# radio-v3_2.net
KiCad netlist of a schematic drawn in EAGLE
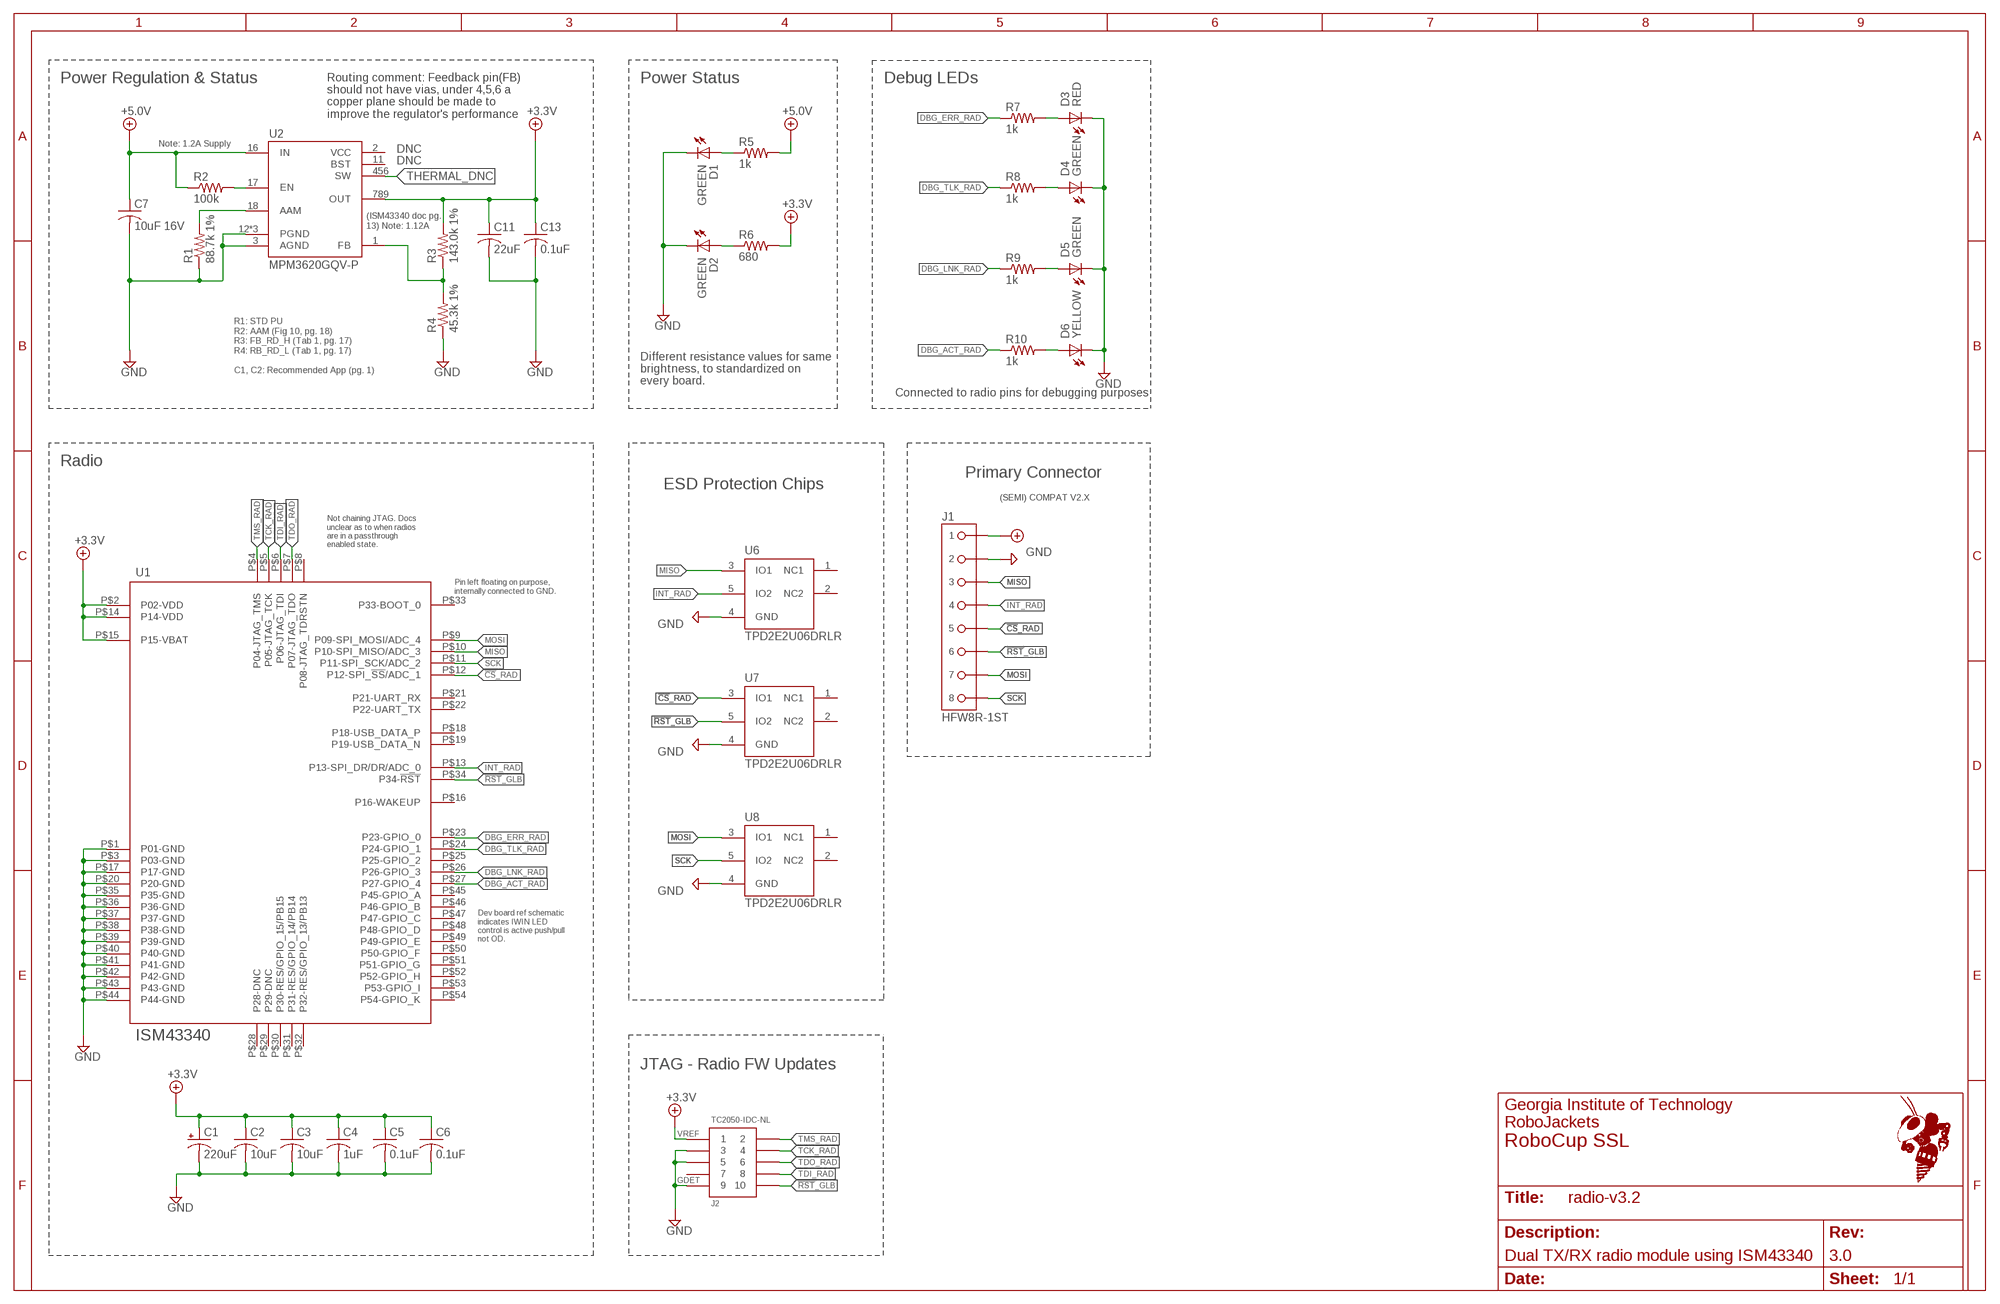
[diagram p0: schematic, sheet 1]

(export (version "E")
  (design (tool "Eeschema 10.0.6"))
  (components
    (comp (ref "C1")
      (value "220uF")
      (footprint "eagle-import:ECA-0JM221-HGT_HORIZ")
      (fields (field (name "MANUFACTURER_PART_NUMBER") "ECA-1HHG221"))
      (libsource (lib "eagle-import") (part "ECA-0JM221"))
    )
    (comp (ref "C2")
      (value "10uF")
      (footprint "eagle-import:C0805")
      (libsource (lib "eagle-import") (part "C-USC0805"))
    )
    (comp (ref "C3")
      (value "10uF")
      (footprint "eagle-import:C0805")
      (libsource (lib "eagle-import") (part "C-USC0805"))
    )
    (comp (ref "C4")
      (value "1uF")
      (footprint "eagle-import:C0603")
      (libsource (lib "eagle-import") (part "C-USC0603"))
    )
    (comp (ref "C5")
      (value "0.1uF")
      (footprint "eagle-import:C0603")
      (libsource (lib "eagle-import") (part "C-USC0603"))
    )
    (comp (ref "C6")
      (value "0.1uF")
      (footprint "eagle-import:C0603")
      (libsource (lib "eagle-import") (part "C-USC0603"))
    )
    (comp (ref "C7")
      (value "10uF 16V")
      (footprint "eagle-import:C1210")
      (libsource (lib "eagle-import") (part "C-USC1210"))
    )
    (comp (ref "C11")
      (value "22uF")
      (footprint "eagle-import:C1210")
      (libsource (lib "eagle-import") (part "C-USC1210"))
    )
    (comp (ref "C13")
      (value "0.1uF")
      (footprint "eagle-import:C0603")
      (libsource (lib "eagle-import") (part "C-USC0603"))
    )
    (comp (ref "D1")
      (value "GREEN")
      (footprint "eagle-import:CHIP-LED0603")
      (fields (field (name "MPN") "LTST-C191KGKT"))
      (libsource (lib "eagle-import") (part "LED-SMD-GREEN"))
    )
    (comp (ref "D2")
      (value "GREEN")
      (footprint "eagle-import:CHIP-LED0603")
      (fields (field (name "MPN") "LTST-C191KGKT"))
      (libsource (lib "eagle-import") (part "LED-SMD-GREEN"))
    )
    (comp (ref "D3")
      (value "RED")
      (footprint "eagle-import:CHIP-LED0603")
      (fields (field (name "MPN") "LTST-C191KRKT"))
      (libsource (lib "eagle-import") (part "LED-SMD-RED"))
    )
    (comp (ref "D4")
      (value "GREEN")
      (footprint "eagle-import:CHIP-LED0603")
      (fields (field (name "MPN") "LTST-C191KGKT"))
      (libsource (lib "eagle-import") (part "LED-SMD-GREEN"))
    )
    (comp (ref "D5")
      (value "GREEN")
      (footprint "eagle-import:CHIP-LED0603")
      (fields (field (name "MPN") "LTST-C191KGKT"))
      (libsource (lib "eagle-import") (part "LED-SMD-GREEN"))
    )
    (comp (ref "D6")
      (value "YELLOW")
      (footprint "eagle-import:CHIP-LED0603")
      (fields (field (name "MPN") "LTST-C191KSKT"))
      (libsource (lib "eagle-import") (part "LED-SMD-YELLOW"))
    )
    (comp (ref "J1")
      (value "HFW8R-1ST")
      (footprint "eagle-import:HFW8R-1ST")
      (fields (field (name "MPN") "HFW8R-1STE1LF"))
      (libsource (lib "eagle-import") (part "HFW8R-1ST"))
    )
    (comp (ref "J2")
      (value "TC2050-IDC-NL")
      (footprint "eagle-import:TC2050-IDC-NL")
      (libsource (lib "eagle-import") (part "TC2050-IDC-NL"))
    )
    (comp (ref "R1")
      (value "88.7k 1%")
      (footprint "eagle-import:R0603")
      (libsource (lib "eagle-import") (part "R-US_R0603"))
    )
    (comp (ref "R2")
      (value "100k")
      (footprint "eagle-import:R0603")
      (libsource (lib "eagle-import") (part "R-US_R0603"))
    )
    (comp (ref "R3")
      (value "143.0k 1%")
      (footprint "eagle-import:R0603")
      (libsource (lib "eagle-import") (part "R-US_R0603"))
    )
    (comp (ref "R4")
      (value "45.3k 1%")
      (footprint "eagle-import:R0603")
      (libsource (lib "eagle-import") (part "R-US_R0603"))
    )
    (comp (ref "R5")
      (value "1k")
      (footprint "eagle-import:R0603")
      (libsource (lib "eagle-import") (part "R-US_R0603"))
    )
    (comp (ref "R6")
      (value "680")
      (footprint "eagle-import:R0603")
      (libsource (lib "eagle-import") (part "R-US_R0603"))
    )
    (comp (ref "R7")
      (value "1k")
      (footprint "eagle-import:R0603")
      (libsource (lib "eagle-import") (part "R-US_R0603"))
    )
    (comp (ref "R8")
      (value "1k")
      (footprint "eagle-import:R0603")
      (libsource (lib "eagle-import") (part "R-US_R0603"))
    )
    (comp (ref "R9")
      (value "1k")
      (footprint "eagle-import:R0603")
      (libsource (lib "eagle-import") (part "R-US_R0603"))
    )
    (comp (ref "R10")
      (value "1k")
      (footprint "eagle-import:R0603")
      (libsource (lib "eagle-import") (part "R-US_R0603"))
    )
    (comp (ref "U1")
      (value "ISM43340")
      (footprint "eagle-import:ISM43340")
      (libsource (lib "eagle-import") (part "ISM43340"))
    )
    (comp (ref "U2")
      (value "MPM3620GQV-P")
      (footprint "eagle-import:MPM3620GQV-P")
      (libsource (lib "eagle-import") (part "MPM3620GQV-P"))
    )
    (comp (ref "U6")
      (value "TPD2E2U06DRLR")
      (footprint "eagle-import:SOT-553")
      (libsource (lib "eagle-import") (part "TPD2E2U06DRLR"))
    )
    (comp (ref "U7")
      (value "TPD2E2U06DRLR")
      (footprint "eagle-import:SOT-553")
      (libsource (lib "eagle-import") (part "TPD2E2U06DRLR"))
    )
    (comp (ref "U8")
      (value "TPD2E2U06DRLR")
      (footprint "eagle-import:SOT-553")
      (libsource (lib "eagle-import") (part "TPD2E2U06DRLR"))
    )
  )
  (nets
    (net (code "1") (name "+3.3V") (class "Default")
      (node (ref "C1") (pin "P$1") (pinfunction "+_P$1") (pintype "passive"))
      (node (ref "C11") (pin "1") (pinfunction "1_1") (pintype "passive"))
      (node (ref "C13") (pin "1") (pinfunction "1_1") (pintype "passive"))
      (node (ref "C2") (pin "1") (pinfunction "1_1") (pintype "passive"))
      (node (ref "C3") (pin "1") (pinfunction "1_1") (pintype "passive"))
      (node (ref "C4") (pin "1") (pinfunction "1_1") (pintype "passive"))
      (node (ref "C5") (pin "1") (pinfunction "1_1") (pintype "passive"))
      (node (ref "C6") (pin "1") (pinfunction "1_1") (pintype "passive"))
      (node (ref "J2") (pin "P$1") (pinfunction "1_P$1") (pintype "bidirectional"))
      (node (ref "R3") (pin "2") (pinfunction "2_2") (pintype "passive"))
      (node (ref "R6") (pin "2") (pinfunction "2_2") (pintype "passive"))
      (node (ref "U1") (pin "P$14") (pinfunction "P14-VDD_P$14") (pintype "bidirectional"))
      (node (ref "U1") (pin "P$15") (pinfunction "P15-VBAT_P$15") (pintype "bidirectional"))
      (node (ref "U1") (pin "P$2") (pinfunction "P02-VDD_P$2") (pintype "bidirectional"))
      (node (ref "U2") (pin "789") (pinfunction "OUT_789") (pintype "bidirectional"))
    )
    (net (code "2") (name "+5.0V") (class "Default")
      (node (ref "C7") (pin "1") (pinfunction "1_1") (pintype "passive"))
      (node (ref "J1") (pin "1") (pinfunction "1_1") (pintype "passive"))
      (node (ref "R2") (pin "1") (pinfunction "1_1") (pintype "passive"))
      (node (ref "R5") (pin "2") (pinfunction "2_2") (pintype "passive"))
      (node (ref "U2") (pin "16") (pinfunction "IN_16") (pintype "bidirectional"))
    )
    (net (code "3") (name "/~{CS}_RAD") (class "Default")
      (node (ref "J1") (pin "5") (pinfunction "5_5") (pintype "passive"))
      (node (ref "U1") (pin "P$12") (pinfunction "P12-SPI_~{SS}/ADC_1_P$12") (pintype "bidirectional"))
      (node (ref "U7") (pin "3") (pinfunction "IO1_3") (pintype "bidirectional"))
    )
    (net (code "4") (name "/~{RST}_GLB") (class "Default")
      (node (ref "J1") (pin "6") (pinfunction "6_6") (pintype "passive"))
      (node (ref "J2") (pin "P$10") (pinfunction "10_P$10") (pintype "bidirectional"))
      (node (ref "U1") (pin "P$34") (pinfunction "P34-~{RST}_P$34") (pintype "bidirectional"))
      (node (ref "U7") (pin "5") (pinfunction "IO2_5") (pintype "bidirectional"))
    )
    (net (code "5") (name "DBG_ACT_RAD") (class "Default")
      (node (ref "R10") (pin "1") (pinfunction "1_1") (pintype "passive"))
      (node (ref "U1") (pin "P$27") (pinfunction "P27-GPIO_4_P$27") (pintype "bidirectional"))
    )
    (net (code "6") (name "DBG_ERR_RAD") (class "Default")
      (node (ref "R7") (pin "1") (pinfunction "1_1") (pintype "passive"))
      (node (ref "U1") (pin "P$23") (pinfunction "P23-GPIO_0_P$23") (pintype "bidirectional"))
    )
    (net (code "7") (name "DBG_LNK_RAD") (class "Default")
      (node (ref "R9") (pin "1") (pinfunction "1_1") (pintype "passive"))
      (node (ref "U1") (pin "P$26") (pinfunction "P26-GPIO_3_P$26") (pintype "bidirectional"))
    )
    (net (code "8") (name "DBG_TLK_RAD") (class "Default")
      (node (ref "R8") (pin "1") (pinfunction "1_1") (pintype "passive"))
      (node (ref "U1") (pin "P$24") (pinfunction "P24-GPIO_1_P$24") (pintype "bidirectional"))
    )
    (net (code "9") (name "GND") (class "Default")
      (node (ref "C1") (pin "P$2") (pinfunction "-_P$2") (pintype "passive"))
      (node (ref "C11") (pin "2") (pinfunction "2_2") (pintype "passive"))
      (node (ref "C13") (pin "2") (pinfunction "2_2") (pintype "passive"))
      (node (ref "C2") (pin "2") (pinfunction "2_2") (pintype "passive"))
      (node (ref "C3") (pin "2") (pinfunction "2_2") (pintype "passive"))
      (node (ref "C4") (pin "2") (pinfunction "2_2") (pintype "passive"))
      (node (ref "C5") (pin "2") (pinfunction "2_2") (pintype "passive"))
      (node (ref "C6") (pin "2") (pinfunction "2_2") (pintype "passive"))
      (node (ref "C7") (pin "2") (pinfunction "2_2") (pintype "passive"))
      (node (ref "D1") (pin "C") (pinfunction "K_C") (pintype "passive"))
      (node (ref "D2") (pin "C") (pinfunction "K_C") (pintype "passive"))
      (node (ref "D3") (pin "C") (pinfunction "K_C") (pintype "passive"))
      (node (ref "D4") (pin "C") (pinfunction "K_C") (pintype "passive"))
      (node (ref "D5") (pin "C") (pinfunction "K_C") (pintype "passive"))
      (node (ref "D6") (pin "C") (pinfunction "K_C") (pintype "passive"))
      (node (ref "J1") (pin "2") (pinfunction "2_2") (pintype "passive"))
      (node (ref "J2") (pin "P$3") (pinfunction "3_P$3") (pintype "bidirectional"))
      (node (ref "J2") (pin "P$5") (pinfunction "5_P$5") (pintype "bidirectional"))
      (node (ref "J2") (pin "P$9") (pinfunction "9_P$9") (pintype "bidirectional"))
      (node (ref "R1") (pin "1") (pinfunction "1_1") (pintype "passive"))
      (node (ref "R4") (pin "1") (pinfunction "1_1") (pintype "passive"))
      (node (ref "U1") (pin "P$1") (pinfunction "P01-GND_P$1") (pintype "bidirectional"))
      (node (ref "U1") (pin "P$17") (pinfunction "P17-GND_P$17") (pintype "bidirectional"))
      (node (ref "U1") (pin "P$20") (pinfunction "P20-GND_P$20") (pintype "bidirectional"))
      (node (ref "U1") (pin "P$3") (pinfunction "P03-GND_P$3") (pintype "bidirectional"))
      (node (ref "U1") (pin "P$35") (pinfunction "P35-GND_P$35") (pintype "bidirectional"))
      (node (ref "U1") (pin "P$36") (pinfunction "P36-GND_P$36") (pintype "bidirectional"))
      (node (ref "U1") (pin "P$37") (pinfunction "P37-GND_P$37") (pintype "bidirectional"))
      (node (ref "U1") (pin "P$38") (pinfunction "P38-GND_P$38") (pintype "bidirectional"))
      (node (ref "U1") (pin "P$39") (pinfunction "P39-GND_P$39") (pintype "bidirectional"))
      (node (ref "U1") (pin "P$40") (pinfunction "P40-GND_P$40") (pintype "bidirectional"))
      (node (ref "U1") (pin "P$41") (pinfunction "P41-GND_P$41") (pintype "bidirectional"))
      (node (ref "U1") (pin "P$42") (pinfunction "P42-GND_P$42") (pintype "bidirectional"))
      (node (ref "U1") (pin "P$43") (pinfunction "P43-GND_P$43") (pintype "bidirectional"))
      (node (ref "U1") (pin "P$44") (pinfunction "P44-GND_P$44") (pintype "bidirectional"))
      (node (ref "U2") (pin "12") (pinfunction "PGND_12") (pintype "bidirectional"))
      (node (ref "U2") (pin "13") (pinfunction "PGND_13") (pintype "bidirectional"))
      (node (ref "U2") (pin "14") (pinfunction "PGND_14") (pintype "bidirectional"))
      (node (ref "U2") (pin "3") (pinfunction "AGND_3") (pintype "bidirectional"))
      (node (ref "U6") (pin "4") (pinfunction "GND_4") (pintype "power_in"))
      (node (ref "U7") (pin "4") (pinfunction "GND_4") (pintype "power_in"))
      (node (ref "U8") (pin "4") (pinfunction "GND_4") (pintype "power_in"))
    )
    (net (code "10") (name "INT_RAD") (class "Default")
      (node (ref "J1") (pin "4") (pinfunction "4_4") (pintype "passive"))
      (node (ref "U1") (pin "P$13") (pinfunction "P13-SPI_DR/DR/ADC_0_P$13") (pintype "bidirectional"))
      (node (ref "U6") (pin "5") (pinfunction "IO2_5") (pintype "bidirectional"))
    )
    (net (code "11") (name "MISO") (class "Default")
      (node (ref "J1") (pin "3") (pinfunction "3_3") (pintype "passive"))
      (node (ref "U1") (pin "P$10") (pinfunction "P10-SPI_MISO/ADC_3_P$10") (pintype "bidirectional"))
      (node (ref "U6") (pin "3") (pinfunction "IO1_3") (pintype "bidirectional"))
    )
    (net (code "12") (name "MOSI") (class "Default")
      (node (ref "J1") (pin "7") (pinfunction "7_7") (pintype "passive"))
      (node (ref "U1") (pin "P$9") (pinfunction "P09-SPI_MOSI/ADC_4_P$9") (pintype "bidirectional"))
      (node (ref "U8") (pin "3") (pinfunction "IO1_3") (pintype "bidirectional"))
    )
    (net (code "13") (name "Net-(D1-PadA)") (class "Default")
      (node (ref "D1") (pin "A") (pinfunction "A_A") (pintype "passive"))
      (node (ref "R5") (pin "1") (pinfunction "1_1") (pintype "passive"))
    )
    (net (code "14") (name "Net-(D2-PadA)") (class "Default")
      (node (ref "D2") (pin "A") (pinfunction "A_A") (pintype "passive"))
      (node (ref "R6") (pin "1") (pinfunction "1_1") (pintype "passive"))
    )
    (net (code "15") (name "Net-(D3-PadA)") (class "Default")
      (node (ref "D3") (pin "A") (pinfunction "A_A") (pintype "passive"))
      (node (ref "R7") (pin "2") (pinfunction "2_2") (pintype "passive"))
    )
    (net (code "16") (name "Net-(D4-PadA)") (class "Default")
      (node (ref "D4") (pin "A") (pinfunction "A_A") (pintype "passive"))
      (node (ref "R8") (pin "2") (pinfunction "2_2") (pintype "passive"))
    )
    (net (code "17") (name "Net-(D5-PadA)") (class "Default")
      (node (ref "D5") (pin "A") (pinfunction "A_A") (pintype "passive"))
      (node (ref "R9") (pin "2") (pinfunction "2_2") (pintype "passive"))
    )
    (net (code "18") (name "Net-(D6-PadA)") (class "Default")
      (node (ref "D6") (pin "A") (pinfunction "A_A") (pintype "passive"))
      (node (ref "R10") (pin "2") (pinfunction "2_2") (pintype "passive"))
    )
    (net (code "19") (name "Net-(U2-AAM)") (class "Default")
      (node (ref "R1") (pin "2") (pinfunction "2_2") (pintype "passive"))
      (node (ref "U2") (pin "18") (pinfunction "AAM_18") (pintype "bidirectional"))
    )
    (net (code "20") (name "Net-(U2-EN)") (class "Default")
      (node (ref "R2") (pin "2") (pinfunction "2_2") (pintype "passive"))
      (node (ref "U2") (pin "17") (pinfunction "EN_17") (pintype "bidirectional"))
    )
    (net (code "21") (name "Net-(U2-FB)") (class "Default")
      (node (ref "R3") (pin "1") (pinfunction "1_1") (pintype "passive"))
      (node (ref "R4") (pin "2") (pinfunction "2_2") (pintype "passive"))
      (node (ref "U2") (pin "1") (pinfunction "FB_1") (pintype "bidirectional"))
    )
    (net (code "22") (name "SCK") (class "Default")
      (node (ref "J1") (pin "8") (pinfunction "8_8") (pintype "passive"))
      (node (ref "U1") (pin "P$11") (pinfunction "P11-SPI_SCK/ADC_2_P$11") (pintype "bidirectional"))
      (node (ref "U8") (pin "5") (pinfunction "IO2_5") (pintype "bidirectional"))
    )
    (net (code "23") (name "TCK_RAD") (class "Default")
      (node (ref "J2") (pin "P$4") (pinfunction "4_P$4") (pintype "bidirectional"))
      (node (ref "U1") (pin "P$5") (pinfunction "P05-JTAG_TCK_P$5") (pintype "bidirectional"))
    )
    (net (code "24") (name "TDI_RAD") (class "Default")
      (node (ref "J2") (pin "P$8") (pinfunction "8_P$8") (pintype "bidirectional"))
      (node (ref "U1") (pin "P$6") (pinfunction "P06-JTAG_TDI_P$6") (pintype "bidirectional"))
    )
    (net (code "25") (name "TDO_RAD") (class "Default")
      (node (ref "J2") (pin "P$6") (pinfunction "6_P$6") (pintype "bidirectional"))
      (node (ref "U1") (pin "P$7") (pinfunction "P07-JTAG_TDO_P$7") (pintype "bidirectional"))
    )
    (net (code "26") (name "THERMAL_DNC") (class "Default")
      (node (ref "U2") (pin "456") (pinfunction "SW_456") (pintype "bidirectional"))
    )
    (net (code "27") (name "TMS_RAD") (class "Default")
      (node (ref "J2") (pin "P$2") (pinfunction "2_P$2") (pintype "bidirectional"))
      (node (ref "U1") (pin "P$4") (pinfunction "P04-JTAG_TMS_P$4") (pintype "bidirectional"))
    )
    (net (code "28") (name "unconnected-(J2-7-PadP$7)") (class "Default")
      (node (ref "J2") (pin "P$7") (pinfunction "7_P$7") (pintype "bidirectional"))
    )
    (net (code "29") (name "unconnected-(U1-P08-JTAG_TDRSTN-PadP$8)") (class "Default")
      (node (ref "U1") (pin "P$8") (pinfunction "P08-JTAG_TDRSTN_P$8") (pintype "bidirectional"))
    )
    (net (code "30") (name "unconnected-(U1-P16-WAKEUP-PadP$16)") (class "Default")
      (node (ref "U1") (pin "P$16") (pinfunction "P16-WAKEUP_P$16") (pintype "bidirectional"))
    )
    (net (code "31") (name "unconnected-(U1-P18-USB_DATA_P-PadP$18)") (class "Default")
      (node (ref "U1") (pin "P$18") (pinfunction "P18-USB_DATA_P_P$18") (pintype "bidirectional"))
    )
    (net (code "32") (name "unconnected-(U1-P19-USB_DATA_N-PadP$19)") (class "Default")
      (node (ref "U1") (pin "P$19") (pinfunction "P19-USB_DATA_N_P$19") (pintype "bidirectional"))
    )
    (net (code "33") (name "unconnected-(U1-P21-UART_RX-PadP$21)") (class "Default")
      (node (ref "U1") (pin "P$21") (pinfunction "P21-UART_RX_P$21") (pintype "bidirectional"))
    )
    (net (code "34") (name "unconnected-(U1-P22-UART_TX-PadP$22)") (class "Default")
      (node (ref "U1") (pin "P$22") (pinfunction "P22-UART_TX_P$22") (pintype "bidirectional"))
    )
    (net (code "35") (name "unconnected-(U1-P25-GPIO_2-PadP$25)") (class "Default")
      (node (ref "U1") (pin "P$25") (pinfunction "P25-GPIO_2_P$25") (pintype "bidirectional"))
    )
    (net (code "36") (name "unconnected-(U1-P28-DNC-PadP$28)") (class "Default")
      (node (ref "U1") (pin "P$28") (pinfunction "P28-DNC_P$28") (pintype "bidirectional"))
    )
    (net (code "37") (name "unconnected-(U1-P29-DNC-PadP$29)") (class "Default")
      (node (ref "U1") (pin "P$29") (pinfunction "P29-DNC_P$29") (pintype "bidirectional"))
    )
    (net (code "38") (name "unconnected-(U1-P30-RES{slash}GPIO_15{slash}PB15-PadP$30)") (class "Default")
      (node (ref "U1") (pin "P$30") (pinfunction "P30-RES/GPIO_15/PB15_P$30") (pintype "bidirectional"))
    )
    (net (code "39") (name "unconnected-(U1-P31-RES{slash}GPIO_14{slash}PB14-PadP$31)") (class "Default")
      (node (ref "U1") (pin "P$31") (pinfunction "P31-RES/GPIO_14/PB14_P$31") (pintype "bidirectional"))
    )
    (net (code "40") (name "unconnected-(U1-P32-RES{slash}GPIO_13{slash}PB13-PadP$32)") (class "Default")
      (node (ref "U1") (pin "P$32") (pinfunction "P32-RES/GPIO_13/PB13_P$32") (pintype "bidirectional"))
    )
    (net (code "41") (name "unconnected-(U1-P33-BOOT_0-PadP$33)") (class "Default")
      (node (ref "U1") (pin "P$33") (pinfunction "P33-BOOT_0_P$33") (pintype "bidirectional"))
    )
    (net (code "42") (name "unconnected-(U1-P45-GPIO_A-PadP$45)") (class "Default")
      (node (ref "U1") (pin "P$45") (pinfunction "P45-GPIO_A_P$45") (pintype "bidirectional"))
    )
    (net (code "43") (name "unconnected-(U1-P46-GPIO_B-PadP$46)") (class "Default")
      (node (ref "U1") (pin "P$46") (pinfunction "P46-GPIO_B_P$46") (pintype "bidirectional"))
    )
    (net (code "44") (name "unconnected-(U1-P47-GPIO_C-PadP$47)") (class "Default")
      (node (ref "U1") (pin "P$47") (pinfunction "P47-GPIO_C_P$47") (pintype "bidirectional"))
    )
    (net (code "45") (name "unconnected-(U1-P48-GPIO_D-PadP$48)") (class "Default")
      (node (ref "U1") (pin "P$48") (pinfunction "P48-GPIO_D_P$48") (pintype "bidirectional"))
    )
    (net (code "46") (name "unconnected-(U1-P49-GPIO_E-PadP$49)") (class "Default")
      (node (ref "U1") (pin "P$49") (pinfunction "P49-GPIO_E_P$49") (pintype "bidirectional"))
    )
    (net (code "47") (name "unconnected-(U1-P50-GPIO_F-PadP$50)") (class "Default")
      (node (ref "U1") (pin "P$50") (pinfunction "P50-GPIO_F_P$50") (pintype "bidirectional"))
    )
    (net (code "48") (name "unconnected-(U1-P51-GPIO_G-PadP$51)") (class "Default")
      (node (ref "U1") (pin "P$51") (pinfunction "P51-GPIO_G_P$51") (pintype "bidirectional"))
    )
    (net (code "49") (name "unconnected-(U1-P52-GPIO_H-PadP$52)") (class "Default")
      (node (ref "U1") (pin "P$52") (pinfunction "P52-GPIO_H_P$52") (pintype "bidirectional"))
    )
    (net (code "50") (name "unconnected-(U1-P53-GPIO_I-PadP$53)") (class "Default")
      (node (ref "U1") (pin "P$53") (pinfunction "P53-GPIO_I_P$53") (pintype "bidirectional"))
    )
    (net (code "51") (name "unconnected-(U1-P54-GPIO_K-PadP$54)") (class "Default")
      (node (ref "U1") (pin "P$54") (pinfunction "P54-GPIO_K_P$54") (pintype "bidirectional"))
    )
    (net (code "52") (name "unconnected-(U2-BST-Pad11)") (class "Default")
      (node (ref "U2") (pin "11") (pinfunction "BST_11") (pintype "bidirectional"))
    )
    (net (code "53") (name "unconnected-(U2-VCC-Pad2)") (class "Default")
      (node (ref "U2") (pin "2") (pinfunction "VCC_2") (pintype "bidirectional"))
    )
    (net (code "54") (name "unconnected-(U6-NC1-Pad1)") (class "Default")
      (node (ref "U6") (pin "1") (pinfunction "NC1_1") (pintype "no_connect"))
    )
    (net (code "55") (name "unconnected-(U6-NC2-Pad2)") (class "Default")
      (node (ref "U6") (pin "2") (pinfunction "NC2_2") (pintype "no_connect"))
    )
    (net (code "56") (name "unconnected-(U7-NC1-Pad1)") (class "Default")
      (node (ref "U7") (pin "1") (pinfunction "NC1_1") (pintype "no_connect"))
    )
    (net (code "57") (name "unconnected-(U7-NC2-Pad2)") (class "Default")
      (node (ref "U7") (pin "2") (pinfunction "NC2_2") (pintype "no_connect"))
    )
    (net (code "58") (name "unconnected-(U8-NC1-Pad1)") (class "Default")
      (node (ref "U8") (pin "1") (pinfunction "NC1_1") (pintype "no_connect"))
    )
    (net (code "59") (name "unconnected-(U8-NC2-Pad2)") (class "Default")
      (node (ref "U8") (pin "2") (pinfunction "NC2_2") (pintype "no_connect"))
    )
  )
)
